# Spannungsregulator_stromueberhohung.net
KiCad netlist of a schematic drawn in EAGLE
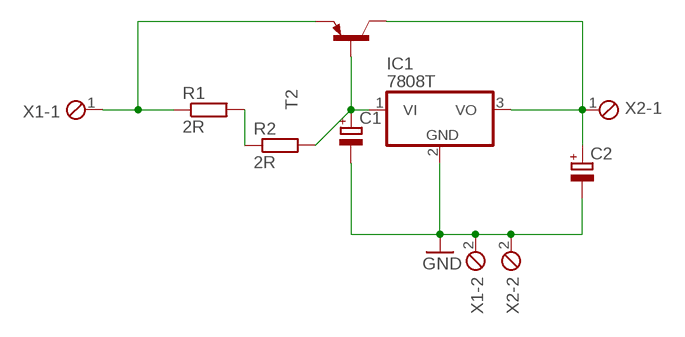
[diagram p0: schematic, sheet 1]

(export (version "E")
  (design (tool "Eeschema 10.0.6"))
  (components
    (comp (ref "C1")
      (value "CPOL-EUE2,5-6E")
      (footprint "eagle-import:E2,5-6E")
      (libsource (lib "eagle-import") (part "CPOL-EUE2,5-6E"))
    )
    (comp (ref "C2")
      (value "CPOL-EUE2,5-6E")
      (footprint "eagle-import:E2,5-6E")
      (libsource (lib "eagle-import") (part "CPOL-EUE2,5-6E"))
    )
    (comp (ref "IC1")
      (value "7808T")
      (footprint "eagle-import:TO220H")
      (libsource (lib "eagle-import") (part "78T08"))
    )
    (comp (ref "R1")
      (value "2R")
      (footprint "eagle-import:0204_7")
      (libsource (lib "eagle-import") (part "R-EU_0204/7"))
    )
    (comp (ref "R2")
      (value "2R")
      (footprint "eagle-import:0204_7")
      (libsource (lib "eagle-import") (part "R-EU_0204/7"))
    )
    (comp (ref "T2")
      (value "-PNP-TO220V")
      (footprint "eagle-import:TO220V")
      (libsource (lib "eagle-import") (part "-PNP-TO220V"))
    )
    (comp (ref "X1")
      (value "MPT2")
      (footprint "eagle-import:2POL254")
      (libsource (lib "eagle-import") (part "MPT2"))
    )
    (comp (ref "X2")
      (value "MPT2")
      (footprint "eagle-import:2POL254")
      (libsource (lib "eagle-import") (part "MPT2"))
    )
  )
  (nets
    (net (code "1") (name "GND") (class "Default")
      (node (ref "C1") (pin "-") (pinfunction "-_-") (pintype "passive"))
      (node (ref "C2") (pin "-") (pinfunction "-_-") (pintype "passive"))
      (node (ref "IC1") (pin "2") (pinfunction "GND_2") (pintype "passive"))
      (node (ref "X1") (pin "2") (pinfunction "1_2") (pintype "passive"))
      (node (ref "X2") (pin "2") (pinfunction "1_2") (pintype "passive"))
    )
    (net (code "2") (name "Net-(IC1-VI)") (class "Default")
      (node (ref "C1") (pin "+") (pinfunction "+_+") (pintype "passive"))
      (node (ref "IC1") (pin "1") (pinfunction "VI_1") (pintype "input"))
      (node (ref "R2") (pin "2") (pinfunction "2_2") (pintype "passive"))
      (node (ref "T2") (pin "1") (pinfunction "B_1") (pintype "passive"))
    )
    (net (code "3") (name "Net-(IC1-VO)") (class "Default")
      (node (ref "C2") (pin "+") (pinfunction "+_+") (pintype "passive"))
      (node (ref "IC1") (pin "3") (pinfunction "VO_3") (pintype "passive"))
      (node (ref "T2") (pin "2") (pinfunction "C_2") (pintype "passive"))
      (node (ref "X2") (pin "1") (pinfunction "1_1") (pintype "passive"))
    )
    (net (code "4") (name "Net-(R1-Pad2)") (class "Default")
      (node (ref "R1") (pin "2") (pinfunction "2_2") (pintype "passive"))
      (node (ref "R2") (pin "1") (pinfunction "1_1") (pintype "passive"))
    )
    (net (code "5") (name "Net-(T2-E)") (class "Default")
      (node (ref "R1") (pin "1") (pinfunction "1_1") (pintype "passive"))
      (node (ref "T2") (pin "3") (pinfunction "E_3") (pintype "passive"))
      (node (ref "X1") (pin "1") (pinfunction "1_1") (pintype "passive"))
    )
  )
)
